# Relay_driver.net
KiCad netlist of a schematic drawn in EAGLE
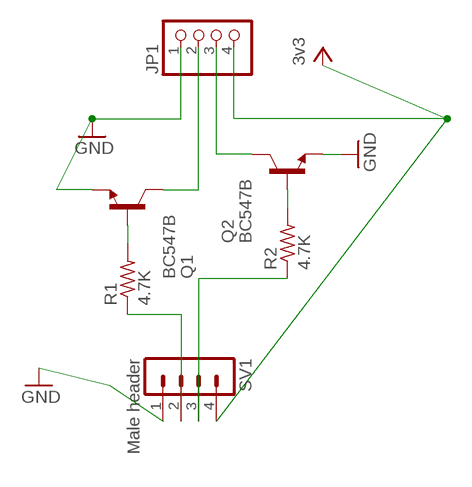
[diagram p0: schematic, sheet 1]

(export (version "E")
  (design (tool "Eeschema 10.0.6"))
  (components
    (comp (ref "JP1")
      (value "PINHD-1X4")
      (footprint "eagle-import:1X04")
      (libsource (lib "eagle-import") (part "PINHD-1X4"))
    )
    (comp (ref "Q1")
      (value "BC547B")
      (footprint "eagle-import:TO92")
      (libsource (lib "eagle-import") (part "BC547B"))
    )
    (comp (ref "Q2")
      (value "BC547B")
      (footprint "eagle-import:TO92")
      (libsource (lib "eagle-import") (part "BC547B"))
    )
    (comp (ref "R1")
      (value "4.7K")
      (footprint "eagle-import:0204_5")
      (libsource (lib "eagle-import") (part "R-US_0204/5"))
    )
    (comp (ref "R2")
      (value "4.7K")
      (footprint "eagle-import:0204_5")
      (libsource (lib "eagle-import") (part "R-US_0204/5"))
    )
    (comp (ref "SV1")
      (value "Male header")
      (footprint "eagle-import:MA04-1")
      (libsource (lib "eagle-import") (part "MA04-1"))
    )
  )
  (nets
    (net (code "1") (name "3v3") (class "Default")
      (node (ref "JP1") (pin "4") (pinfunction "4_4") (pintype "passive"))
      (node (ref "SV1") (pin "4") (pinfunction "4_4") (pintype "passive"))
    )
    (net (code "2") (name "GND") (class "Default")
      (node (ref "JP1") (pin "1") (pinfunction "1_1") (pintype "passive"))
      (node (ref "Q1") (pin "1") (pinfunction "E_1") (pintype "passive"))
      (node (ref "Q2") (pin "1") (pinfunction "E_1") (pintype "passive"))
      (node (ref "SV1") (pin "1") (pinfunction "1_1") (pintype "passive"))
    )
    (net (code "3") (name "Net-(Q1-B)") (class "Default")
      (node (ref "Q1") (pin "2") (pinfunction "B_2") (pintype "passive"))
      (node (ref "R1") (pin "2") (pinfunction "2_2") (pintype "passive"))
    )
    (net (code "4") (name "Net-(Q1-C)") (class "Default")
      (node (ref "JP1") (pin "2") (pinfunction "2_2") (pintype "passive"))
      (node (ref "Q1") (pin "3") (pinfunction "C_3") (pintype "passive"))
    )
    (net (code "5") (name "Net-(Q2-B)") (class "Default")
      (node (ref "Q2") (pin "2") (pinfunction "B_2") (pintype "passive"))
      (node (ref "R2") (pin "2") (pinfunction "2_2") (pintype "passive"))
    )
    (net (code "6") (name "Net-(Q2-C)") (class "Default")
      (node (ref "JP1") (pin "3") (pinfunction "3_3") (pintype "passive"))
      (node (ref "Q2") (pin "3") (pinfunction "C_3") (pintype "passive"))
    )
    (net (code "7") (name "Net-(R1-Pad1)") (class "Default")
      (node (ref "R1") (pin "1") (pinfunction "1_1") (pintype "passive"))
      (node (ref "SV1") (pin "2") (pinfunction "2_2") (pintype "passive"))
    )
    (net (code "8") (name "Net-(R2-Pad1)") (class "Default")
      (node (ref "R2") (pin "1") (pinfunction "1_1") (pintype "passive"))
      (node (ref "SV1") (pin "3") (pinfunction "3_3") (pintype "passive"))
    )
  )
)
